# S4_Power_Supply.net
KiCad netlist of a schematic drawn in Altium Designer
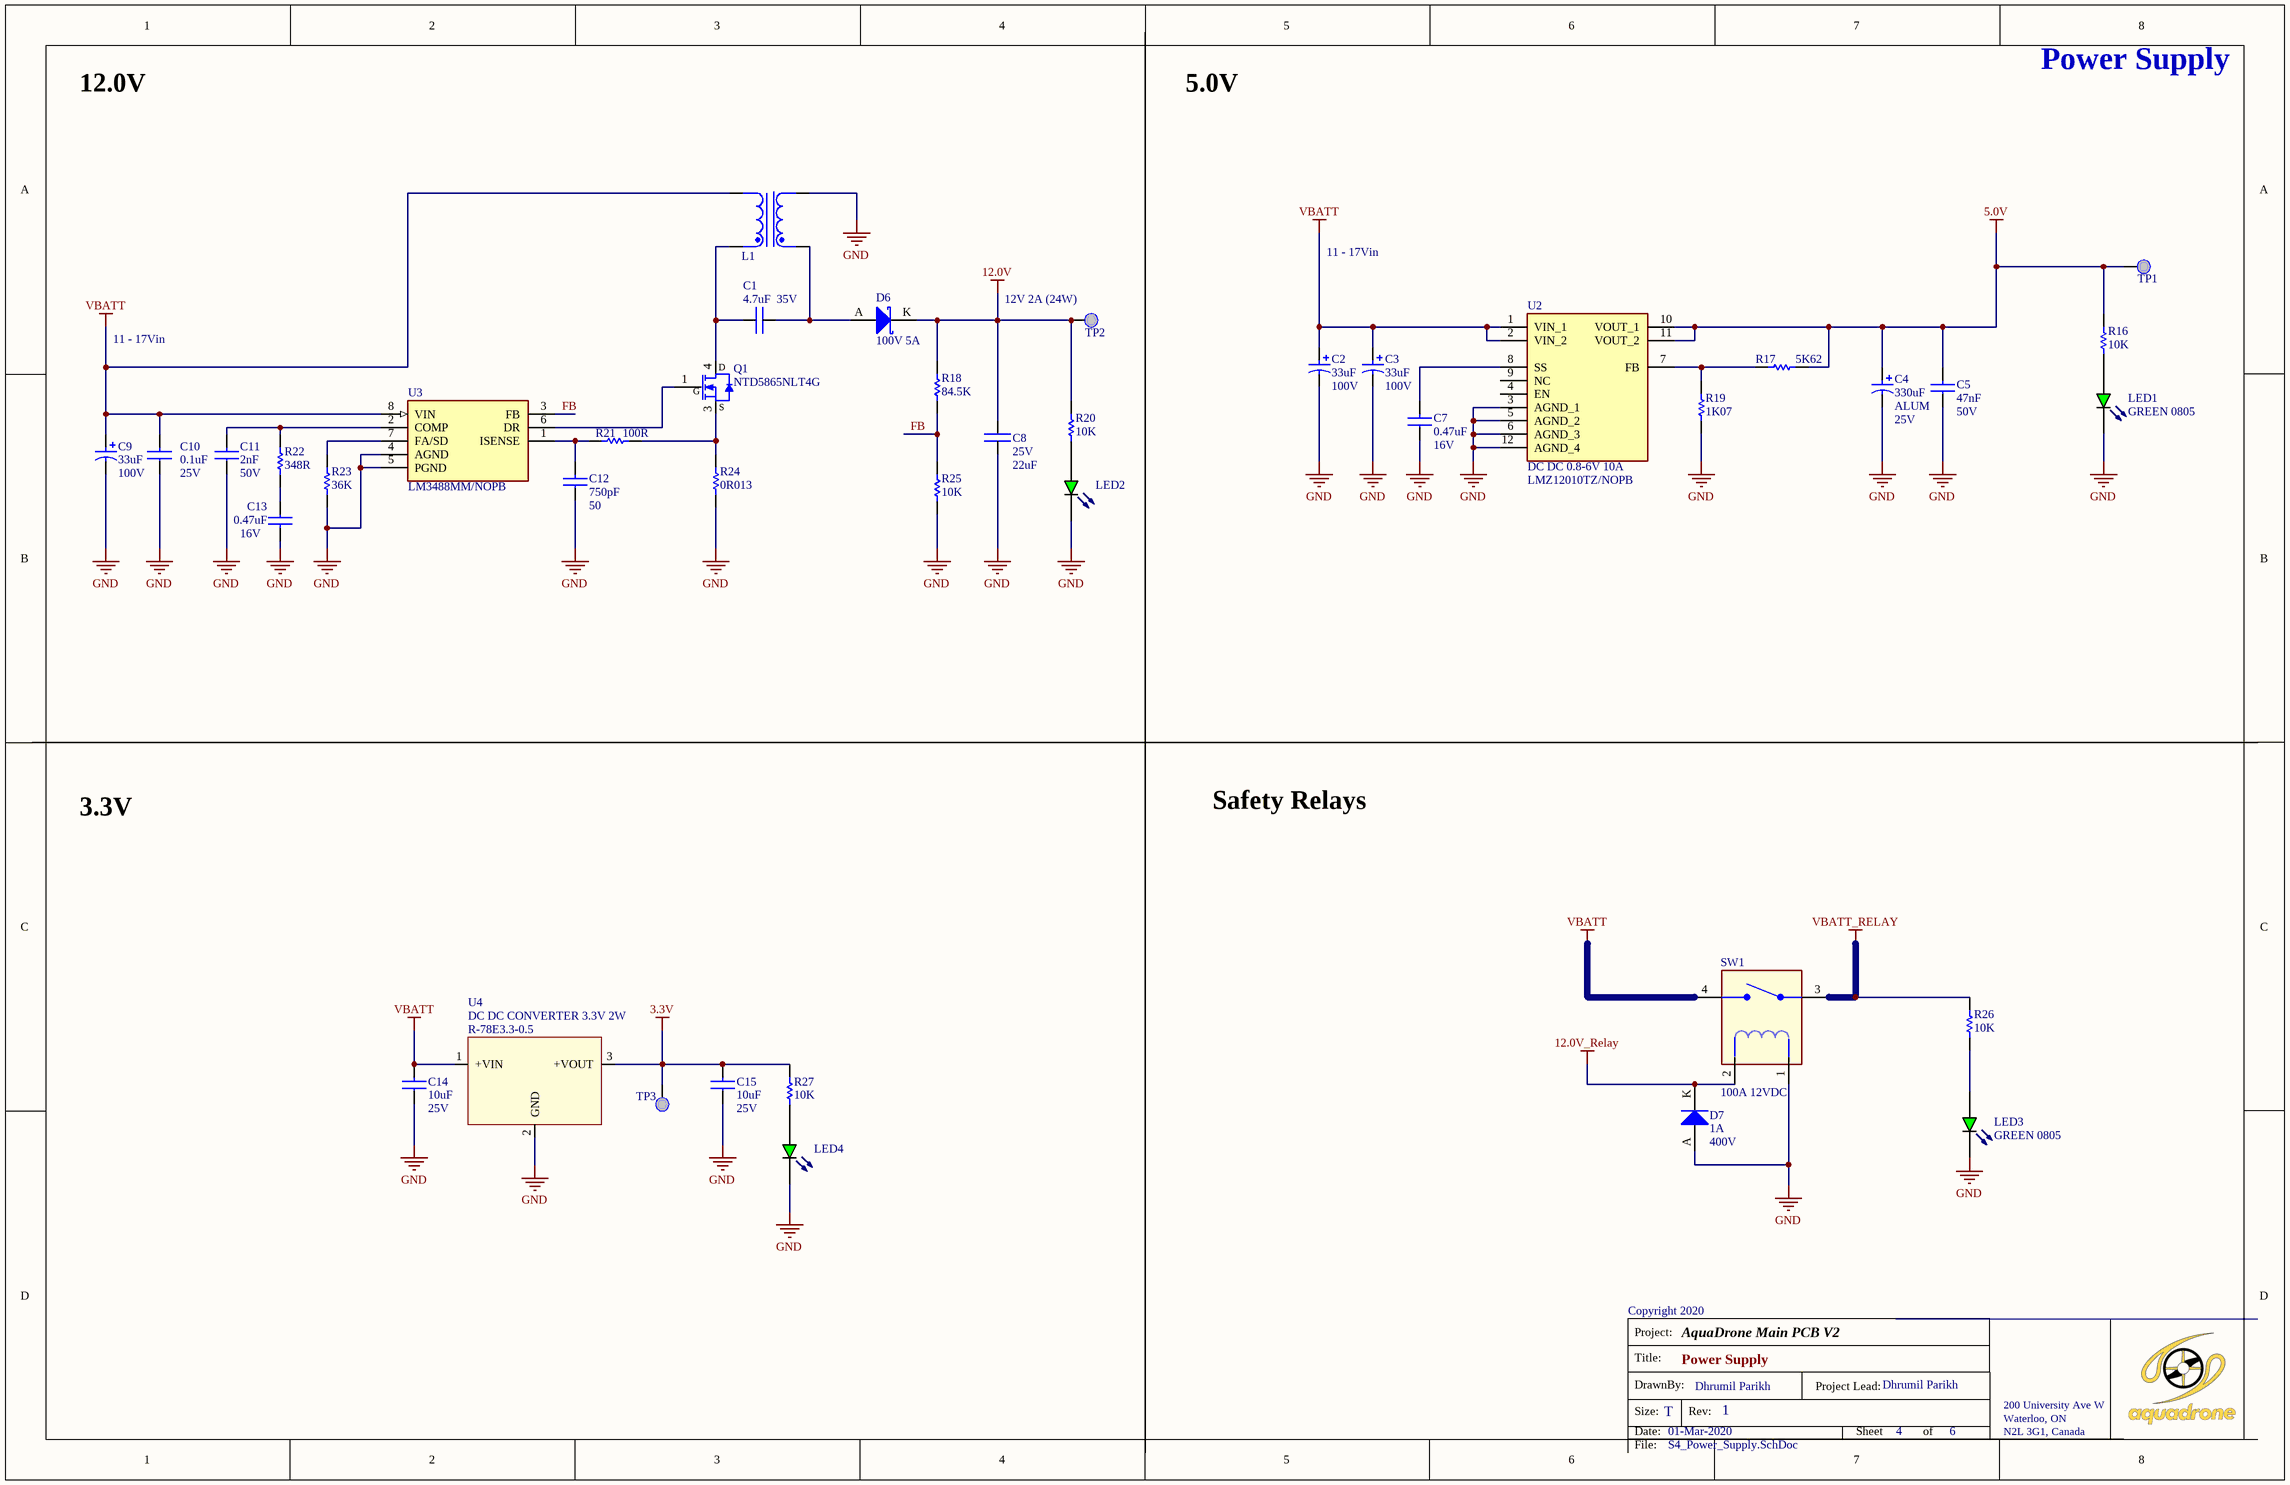
[diagram p0: S4_Power_Supply.SchDoc]

(export (version "E")
  (design (tool "Eeschema 10.0.6"))
  (components
    (comp (ref "C1")
      (value "4.7uF")
      (footprint "RWMN:CAPC2012X14N")
      (description "CAP CER 4.7UF 35V X5R 0805")
      (fields
        (field (name "MFG") "Murata Electronics")
        (field (name "MFG_PART_NO") "GRM219R6YA475KA73D")
        (field (name "VOLTAGE") "35V")
      )
      (libsource (lib "AquaDrone") (part "CAP CER 4.7UF 35V X5R 0805"))
    )
    (comp (ref "C2")
      (value "33uF")
      (footprint "RWMN:CAPPRD350W60D825H1700")
      (description "CAP ALUM 33UF 20% 100V RADIAL")
      (fields
        (field (name "MFG") "Nichicon")
        (field (name "MFG_PART_NO") "UPM2A330MPD1TD")
        (field (name "VOLTAGE") "100V")
      )
      (libsource (lib "AquaDrone") (part "CAP ALUM 33UF 20% 100V RADIAL"))
    )
    (comp (ref "C3")
      (value "33uF")
      (footprint "RWMN:CAPPRD350W60D825H1700")
      (description "CAP ALUM 33UF 20% 100V RADIAL")
      (fields
        (field (name "MFG") "Nichicon")
        (field (name "MFG_PART_NO") "UPM2A330MPD1TD")
        (field (name "VOLTAGE") "100V")
      )
      (libsource (lib "AquaDrone") (part "CAP ALUM 33UF 20% 100V RADIAL"))
    )
    (comp (ref "C4")
      (value "330uF")
      (footprint "RWMN:CAPPRD350W60D850H1300")
      (description "CAP ALUM 330UF 20% 25V TH")
      (fields
        (field (name "MFG") "KEMET")
        (field (name "MFG_PART_NO") "ESL337M025AGMAA")
        (field (name "DIELECTRIC") "ALUM")
        (field (name "VOLTAGE") "25V")
      )
      (libsource (lib "AquaDrone") (part "CAP ALUM 330UF 20% 25V TH"))
    )
    (comp (ref "C5")
      (value "47nF")
      (footprint "RWMN:CAPC1608X09N")
      (description "CAP CER 0.047UF 50V X7R 0603")
      (fields
        (field (name "MFG") "Yageo")
        (field (name "MFG_PART_NO") "CC0603KRX7R9BB473")
        (field (name "VOLTAGE") "50V")
      )
      (libsource (lib "AquaDrone") (part "CAP CER 0.047UF 50V X7R 0603"))
    )
    (comp (ref "C7")
      (value "0.47uF")
      (footprint "RWMN:CAPC1608X09N")
      (description "CAP CER 0.47UF 16V X7R 0603")
      (fields
        (field (name "MFG") "Samsung")
        (field (name "MFG_PART_NO") "CL10B474KO8NNNC")
        (field (name "VOLTAGE") "16V")
      )
      (libsource (lib "AquaDrone") (part "CAP CER 0.47UF 16V X7R 0603"))
    )
    (comp (ref "C8")
      (value "22uF")
      (footprint "RWMN:CAPC3225X28N")
      (description "CAP CER 22UF 25V X7R 1210")
      (fields
        (field (name "MFG") "Taiyo Yuden")
        (field (name "MFG_PART_NO") "TMK325B7226KMHP")
        (field (name "VOLTAGE") "25V")
      )
      (libsource (lib "AquaDrone") (part "CAP CER 22UF 25V X7R 1210"))
    )
    (comp (ref "C9")
      (value "33uF")
      (footprint "RWMN:CAPPRD350W60D825H1700")
      (description "CAP ALUM 33UF 20% 100V RADIAL")
      (fields
        (field (name "MFG") "Nichicon")
        (field (name "MFG_PART_NO") "UPM2A330MPD1TD")
        (field (name "VOLTAGE") "100V")
      )
      (libsource (lib "AquaDrone") (part "CAP ALUM 33UF 20% 100V RADIAL"))
    )
    (comp (ref "C10")
      (value "0.1uF")
      (footprint "RWMN:CAPC1608X09N")
      (description "CAP CER 0.1UF 25V X7R 0603")
      (fields
        (field (name "MFG") "Yageo")
        (field (name "MFG_PART_NO") "CC0603KRX7R8BB104")
        (field (name "VOLTAGE") "25V")
      )
      (libsource (lib "AquaDrone") (part "CAP CER 0.1UF 25V X7R 0603"))
    )
    (comp (ref "C11")
      (value "2nF")
      (footprint "RWMN:CAPC1608X09N")
      (description "CAP CER 2000PF 50V X7R 0603")
      (fields
        (field (name "MFG") "Yageo")
        (field (name "MFG_PART_NO") "CC0603KRX7R9BB202")
        (field (name "VOLTAGE") "50V")
      )
      (libsource (lib "AquaDrone") (part "CAP CER 2000PF 50V X7R 0603"))
    )
    (comp (ref "C12")
      (value "750pF")
      (footprint "RWMN:CAPC1608X09N")
      (description "CAP CER 750PF 50V X7R 0603")
      (fields
        (field (name "MFG") "Yageo")
        (field (name "MFG_PART_NO") "CC0603KRX7R9BB751")
        (field (name "VOLTAGE") "50")
      )
      (libsource (lib "AquaDrone") (part "CAP CER 750PF 50V X7R 0603"))
    )
    (comp (ref "C13")
      (value "0.47uF")
      (footprint "RWMN:CAPC1608X09N")
      (description "CAP CER 0.47UF 16V X7R 0603")
      (fields
        (field (name "MFG") "Samsung")
        (field (name "MFG_PART_NO") "CL10B474KO8NNNC")
        (field (name "VOLTAGE") "16V")
      )
      (libsource (lib "AquaDrone") (part "CAP CER 0.47UF 16V X7R 0603"))
    )
    (comp (ref "C14")
      (value "10uF")
      (footprint "RWMN:CAPC1608X09N")
      (description "CAP CER 10UF 25V X5R 0603")
      (fields
        (field (name "MFG") "KEMET")
        (field (name "MFG_PART_NO") "C1608X5R1E106M080AC")
        (field (name "VOLTAGE") "25V")
      )
      (libsource (lib "AquaDrone") (part "CAP CER 10UF 25V X5R 0603"))
    )
    (comp (ref "C15")
      (value "10uF")
      (footprint "RWMN:CAPC1608X09N")
      (description "CAP CER 10UF 25V X5R 0603")
      (fields
        (field (name "MFG") "KEMET")
        (field (name "MFG_PART_NO") "C1608X5R1E106M080AC")
        (field (name "VOLTAGE") "25V")
      )
      (libsource (lib "AquaDrone") (part "CAP CER 10UF 25V X5R 0603"))
    )
    (comp (ref "D6")
      (value "100V 5A")
      (footprint "SODFL5226X100N")
      (description "DIODE SCHOTTKY 100V 5A DO221AC")
      (fields (field (name "MFG") "Vishay") (field (name "MFG_PART_NO") "VSSAF510-M3/H"))
      (libsource (lib "AquaDrone") (part "DIODE SCHOTTKY 100V 5A DO221AC"))
    )
    (comp (ref "D7")
      (value "DIODE GEN PURP 400V 1A SMA")
      (footprint "DIOM5226X295N")
      (fields
        (field (name "MFG") "SMC Diode Solutions")
        (field (name "MFG_PART_NO") "S1GTR")
        (field (name "CURRENT") "1A")
        (field (name "VR") "400V")
      )
      (libsource (lib "AquaDrone") (part "DIODE GEN PURP 400V 1A SMA"))
    )
    (comp (ref "L1")
      (value "INDUCT ARRAY 2 COIL 9.654UH SMD")
      (footprint "DRQ125100R")
      (fields (field (name "MFG") "Eaton") (field (name "MFG_PART_NO") "DRQ125-100-R"))
      (libsource (lib "AquaDrone") (part "INDUCT ARRAY 2 COIL 9.654UH SMD"))
    )
    (comp (ref "LED1")
      (value "GREEN 0805")
      (footprint "LED0805")
      (description "LED GREEN CLEAR 0805 SMD")
      (fields (field (name "MFG") "Würth Elektronik") (field (name "MFG_PART_NO") "150080VS75000"))
      (libsource (lib "AquaDrone") (part "LED GREEN CLEAR 0805 SMD"))
    )
    (comp (ref "LED2")
      (value "LED GREEN CLEAR 0805 SMD")
      (footprint "LED0805")
      (fields (field (name "MFG") "Würth Elektronik") (field (name "MFG_PART_NO") "150080VS75000"))
      (libsource (lib "AquaDrone") (part "LED GREEN CLEAR 0805 SMD"))
    )
    (comp (ref "LED3")
      (value "GREEN 0805")
      (footprint "LED0805")
      (description "LED GREEN CLEAR 0805 SMD")
      (fields (field (name "MFG") "Würth Elektronik") (field (name "MFG_PART_NO") "150080VS75000"))
      (libsource (lib "AquaDrone") (part "LED GREEN CLEAR 0805 SMD"))
    )
    (comp (ref "LED4")
      (value "LED GREEN CLEAR 0805 SMD")
      (footprint "LED0805")
      (fields (field (name "MFG") "Würth Elektronik") (field (name "MFG_PART_NO") "150080VS75000"))
      (libsource (lib "AquaDrone") (part "LED GREEN CLEAR 0805 SMD"))
    )
    (comp (ref "Q1")
      (value "MOSFET N-CH 60V 46A DPAK")
      (footprint "TO229P990X238-4N")
      (fields (field (name "MFG") "ON Semiconductor") (field (name "MFG_PART_NO") "NTD5865NLT4G"))
      (libsource (lib "AquaDrone") (part "MOSFET N-CH 60V 46A DPAK"))
    )
    (comp (ref "R16")
      (value "10K")
      (footprint "RESC1608X06N")
      (description "RES SMD 10K OHM 1% 1/10W 0603")
      (fields (field (name "MFG") "Vishay Dale") (field (name "MFG_PART_NO") "CRCW060310K0FKEA"))
      (libsource (lib "AquaDrone") (part "RES SMD 10K OHM 1% 1/10W 0603"))
    )
    (comp (ref "R17")
      (value "5K62")
      (footprint "RESC1608X06N")
      (description "RES SMD 5.62K OHM 1% 1/10W 0603")
      (fields (field (name "MFG") "Yageo") (field (name "MFG_PART_NO") "RC0603FR-075K62L"))
      (libsource (lib "AquaDrone") (part "RES SMD 5.62K OHM 1% 1/10W 0603"))
    )
    (comp (ref "R18")
      (value "84.5K")
      (footprint "RESC1608X06N")
      (description "RES SMD 84.5K OHM 1% 1/10W 0603")
      (fields (field (name "MFG") "Yageo") (field (name "MFG_PART_NO") "RC0603FR-0784K5L"))
      (libsource (lib "AquaDrone") (part "RES SMD 84.5K OHM 1% 1/10W 0603"))
    )
    (comp (ref "R19")
      (value "1K07")
      (footprint "RESC1608X06N")
      (description "RES SMD 1.07K OHM 1% 1/10W 0603")
      (fields (field (name "MFG") "Yageo") (field (name "MFG_PART_NO") "RC0603FR-071K07L"))
      (libsource (lib "AquaDrone") (part "RES SMD 1.07K OHM 1% 1/10W 0603"))
    )
    (comp (ref "R20")
      (value "10K")
      (footprint "RESC1608X06N")
      (description "RES SMD 10K OHM 1% 1/10W 0603")
      (fields (field (name "MFG") "Vishay Dale") (field (name "MFG_PART_NO") "CRCW060310K0FKEA"))
      (libsource (lib "AquaDrone") (part "RES SMD 10K OHM 1% 1/10W 0603"))
    )
    (comp (ref "R21")
      (value "100R")
      (footprint "RESC1608X06N")
      (description "RES SMD 100 OHM 1% 1/10W 0603")
      (fields (field (name "MFG") "Yageo") (field (name "MFG_PART_NO") "RC0603FR-07100RL"))
      (libsource (lib "AquaDrone") (part "RES SMD 100 OHM 1% 1/10W 0603"))
    )
    (comp (ref "R22")
      (value "348R")
      (footprint "RESC1608X06N")
      (description "RES SMD 348 OHM 1% 1/10W 0603")
      (fields (field (name "MFG") "Yageo") (field (name "MFG_PART_NO") "RC0603FR-07348RL"))
      (libsource (lib "AquaDrone") (part "RES SMD 348 OHM 1% 1/10W 0603"))
    )
    (comp (ref "R23")
      (value "36K")
      (footprint "RESC1608X06N")
      (description "RES SMD 36K OHM 1% 0.15W 0603")
      (fields (field (name "MFG") "Yageo") (field (name "MFG_PART_NO") "RC0603FR-0736KL"))
      (libsource (lib "AquaDrone") (part "RES SMD 36K OHM 1% 0.15W 0603"))
    )
    (comp (ref "R24")
      (value "0R013")
      (footprint "RESC1632X60N")
      (description "RES 0.013 OHM 1W 1206 WIDE")
      (fields (field (name "MFG") "Susumu") (field (name "MFG_PART_NO") "PRL1632-R013-F-T1"))
      (libsource (lib "AquaDrone") (part "RES 0.013 OHM 1W 1206 WIDE"))
    )
    (comp (ref "R25")
      (value "10K")
      (footprint "RESC1608X06N")
      (description "RES SMD 10K OHM 1% 1/10W 0603")
      (fields (field (name "MFG") "Vishay Dale") (field (name "MFG_PART_NO") "CRCW060310K0FKEA"))
      (libsource (lib "AquaDrone") (part "RES SMD 10K OHM 1% 1/10W 0603"))
    )
    (comp (ref "R26")
      (value "10K")
      (footprint "RESC1608X06N")
      (description "RES SMD 10K OHM 1% 1/10W 0603")
      (fields (field (name "MFG") "Vishay Dale") (field (name "MFG_PART_NO") "CRCW060310K0FKEA"))
      (libsource (lib "AquaDrone") (part "RES SMD 10K OHM 1% 1/10W 0603"))
    )
    (comp (ref "R27")
      (value "10K")
      (footprint "RESC1608X06N")
      (description "RES SMD 10K OHM 1% 1/10W 0603")
      (fields (field (name "MFG") "Vishay Dale") (field (name "MFG_PART_NO") "CRCW060310K0FKEA"))
      (libsource (lib "AquaDrone") (part "RES SMD 10K OHM 1% 1/10W 0603"))
    )
    (comp (ref "SW1")
      (value "100A 12VDC")
      (footprint "G7EB-1A DC12")
      (description "RELAY GEN PURPOSE SPST-NO 100A 12VDC")
      (fields (field (name "MFG") "Omron") (field (name "MFG_PART_NO") "G7EB-1A DC12"))
      (libsource (lib "AquaDrone") (part "RELAY GEN PURPOSE SPST-NO 100A 12VDC"))
    )
    (comp (ref "TP1")
      (value "Testpoint 1mm SMD Pad")
      (footprint "TP_SMD_1.0MM")
      (description "Testpoint 1.0mm SMD Pad")
      (libsource (lib "AquaDrone") (part "Testpoint 1mm SMD Pad"))
    )
    (comp (ref "TP2")
      (value "Testpoint 1mm SMD Pad")
      (footprint "TP_SMD_1.0MM")
      (description "Testpoint 1.0mm SMD Pad")
      (libsource (lib "AquaDrone") (part "Testpoint 1mm SMD Pad"))
    )
    (comp (ref "TP3")
      (value "Testpoint 1mm SMD Pad")
      (footprint "TP_SMD_1.0MM")
      (description "Testpoint 1.0mm SMD Pad")
      (libsource (lib "AquaDrone") (part "Testpoint 1mm SMD Pad"))
    )
    (comp (ref "U2")
      (value "DC DC 0.8-6V 10A")
      (footprint "LMZ12010TZENOPB")
      (description "DC DC CONVERTER 0.8-6V 10A")
      (fields (field (name "MFG") "TI") (field (name "MFG_PART_NO") "LMZ12010TZ/NOPB"))
      (libsource (lib "AquaDrone") (part "DC DC CONVERTER 0.8-6V 10A"))
    )
    (comp (ref "U3")
      (value "IC REG CTRLR MULT TOP 8VSSOP")
      (footprint "SOP65P490X110-8N")
      (fields (field (name "MFG") "TI") (field (name "MFG_PART_NO") "LM3488MM/NOPB"))
      (libsource (lib "AquaDrone") (part "IC REG CTRLR MULT TOP 8VSSOP"))
    )
    (comp (ref "U4")
      (value "DC DC CONVERTER 3.3V 2W")
      (footprint "RWMN:SHDRV3W100P0_254_1X3_1160X850X1040P")
      (fields (field (name "MFG") "Recom Power") (field (name "MFG_PART_NO") "R-78E3.3-0.5"))
      (libsource (lib "AquaDrone") (part "DC DC CONVERTER 3.3V 2W"))
    )
  )
  (nets
    (net (code "1") (name "/FB") (class "Default")
      (node (ref "R18") (pin "1") (pinfunction "1_1") (pintype "passive"))
      (node (ref "R25") (pin "2") (pinfunction "2_2") (pintype "passive"))
      (node (ref "U3") (pin "3") (pinfunction "FB_3") (pintype "passive"))
    )
    (net (code "2") (name "3.3V") (class "Default")
      (node (ref "C15") (pin "2") (pinfunction "2_2") (pintype "passive"))
      (node (ref "R27") (pin "2") (pinfunction "2_2") (pintype "passive"))
      (node (ref "TP3") (pin "1") (pinfunction "1_1") (pintype "passive"))
      (node (ref "U4") (pin "3") (pinfunction "+VOUT_3") (pintype "power_in"))
    )
    (net (code "3") (name "5.0V") (class "Default")
      (node (ref "C4") (pin "1") (pinfunction "1_1") (pintype "passive"))
      (node (ref "C5") (pin "2") (pinfunction "2_2") (pintype "passive"))
      (node (ref "R16") (pin "2") (pinfunction "2_2") (pintype "passive"))
      (node (ref "R17") (pin "2") (pinfunction "2_2") (pintype "passive"))
      (node (ref "TP1") (pin "1") (pinfunction "1_1") (pintype "passive"))
      (node (ref "U2") (pin "10") (pinfunction "VOUT_1_10") (pintype "passive"))
      (node (ref "U2") (pin "11") (pinfunction "VOUT_2_11") (pintype "passive"))
    )
    (net (code "4") (name "12.0V") (class "Default")
      (node (ref "C8") (pin "1") (pinfunction "1_1") (pintype "passive"))
      (node (ref "D6") (pin "K") (pinfunction "K_K") (pintype "passive"))
      (node (ref "R18") (pin "2") (pinfunction "2_2") (pintype "passive"))
      (node (ref "R20") (pin "2") (pinfunction "2_2") (pintype "passive"))
      (node (ref "TP2") (pin "1") (pinfunction "1_1") (pintype "passive"))
    )
    (net (code "5") (name "12.0V_Relay") (class "Default")
      (node (ref "D7") (pin "K") (pinfunction "K_K") (pintype "passive"))
      (node (ref "SW1") (pin "2") (pinfunction "2_2") (pintype "power_in"))
    )
    (net (code "6") (name "GND") (class "Default")
      (node (ref "C10") (pin "1") (pinfunction "1_1") (pintype "passive"))
      (node (ref "C11") (pin "1") (pinfunction "1_1") (pintype "passive"))
      (node (ref "C12") (pin "1") (pinfunction "1_1") (pintype "passive"))
      (node (ref "C13") (pin "2") (pinfunction "2_2") (pintype "passive"))
      (node (ref "C14") (pin "1") (pinfunction "1_1") (pintype "passive"))
      (node (ref "C15") (pin "1") (pinfunction "1_1") (pintype "passive"))
      (node (ref "C2") (pin "2") (pinfunction "2_2") (pintype "passive"))
      (node (ref "C3") (pin "2") (pinfunction "2_2") (pintype "passive"))
      (node (ref "C4") (pin "2") (pinfunction "2_2") (pintype "passive"))
      (node (ref "C5") (pin "1") (pinfunction "1_1") (pintype "passive"))
      (node (ref "C7") (pin "1") (pinfunction "1_1") (pintype "passive"))
      (node (ref "C8") (pin "2") (pinfunction "2_2") (pintype "passive"))
      (node (ref "C9") (pin "2") (pinfunction "2_2") (pintype "passive"))
      (node (ref "D7") (pin "A") (pinfunction "A_A") (pintype "passive"))
      (node (ref "L1") (pin "3") (pinfunction "3_3") (pintype "passive"))
      (node (ref "LED1") (pin "K") (pinfunction "K_K") (pintype "passive"))
      (node (ref "LED2") (pin "K") (pinfunction "K_K") (pintype "passive"))
      (node (ref "LED3") (pin "K") (pinfunction "K_K") (pintype "passive"))
      (node (ref "LED4") (pin "K") (pinfunction "K_K") (pintype "passive"))
      (node (ref "R19") (pin "1") (pinfunction "1_1") (pintype "passive"))
      (node (ref "R23") (pin "1") (pinfunction "1_1") (pintype "passive"))
      (node (ref "R24") (pin "1") (pinfunction "1_1") (pintype "passive"))
      (node (ref "R25") (pin "1") (pinfunction "1_1") (pintype "passive"))
      (node (ref "SW1") (pin "1") (pinfunction "1_1") (pintype "power_in"))
      (node (ref "U2") (pin "12") (pinfunction "AGND_4_12") (pintype "passive"))
      (node (ref "U2") (pin "3") (pinfunction "AGND_1_3") (pintype "passive"))
      (node (ref "U2") (pin "5") (pinfunction "AGND_2_5") (pintype "passive"))
      (node (ref "U2") (pin "6") (pinfunction "AGND_3_6") (pintype "passive"))
      (node (ref "U3") (pin "4") (pinfunction "AGND_4") (pintype "power_in"))
      (node (ref "U3") (pin "5") (pinfunction "PGND_5") (pintype "power_in"))
      (node (ref "U4") (pin "2") (pinfunction "GND_2") (pintype "power_in"))
    )
    (net (code "7") (name "Net-(C1-Pad2)") (class "Default")
      (node (ref "C1") (pin "2") (pinfunction "2_2") (pintype "passive"))
      (node (ref "D6") (pin "A") (pinfunction "A_A") (pintype "passive"))
      (node (ref "L1") (pin "1") (pinfunction "1_1") (pintype "passive"))
    )
    (net (code "8") (name "Net-(C13-Pad1)") (class "Default")
      (node (ref "C13") (pin "1") (pinfunction "1_1") (pintype "passive"))
      (node (ref "R22") (pin "1") (pinfunction "1_1") (pintype "passive"))
    )
    (net (code "9") (name "Net-(LED1-PadA)") (class "Default")
      (node (ref "LED1") (pin "A") (pinfunction "A_A") (pintype "passive"))
      (node (ref "R16") (pin "1") (pinfunction "1_1") (pintype "passive"))
    )
    (net (code "10") (name "Net-(LED2-PadA)") (class "Default")
      (node (ref "LED2") (pin "A") (pinfunction "A_A") (pintype "passive"))
      (node (ref "R20") (pin "1") (pinfunction "1_1") (pintype "passive"))
    )
    (net (code "11") (name "Net-(LED3-PadA)") (class "Default")
      (node (ref "LED3") (pin "A") (pinfunction "A_A") (pintype "passive"))
      (node (ref "R26") (pin "1") (pinfunction "1_1") (pintype "passive"))
    )
    (net (code "12") (name "Net-(LED4-PadA)") (class "Default")
      (node (ref "LED4") (pin "A") (pinfunction "A_A") (pintype "passive"))
      (node (ref "R27") (pin "1") (pinfunction "1_1") (pintype "passive"))
    )
    (net (code "13") (name "Net-(Q1-D)") (class "Default")
      (node (ref "C1") (pin "1") (pinfunction "1_1") (pintype "passive"))
      (node (ref "L1") (pin "2") (pinfunction "2_2") (pintype "passive"))
      (node (ref "Q1") (pin "4") (pinfunction "D_4") (pintype "power_in"))
    )
    (net (code "14") (name "Net-(Q1-G)") (class "Default")
      (node (ref "Q1") (pin "1") (pinfunction "G_1") (pintype "tri_state"))
      (node (ref "U3") (pin "6") (pinfunction "DR_6") (pintype "passive"))
    )
    (net (code "15") (name "Net-(Q1-S)") (class "Default")
      (node (ref "Q1") (pin "3") (pinfunction "S_3") (pintype "power_in"))
      (node (ref "R21") (pin "2") (pinfunction "2_2") (pintype "passive"))
      (node (ref "R24") (pin "2") (pinfunction "2_2") (pintype "passive"))
    )
    (net (code "16") (name "Net-(U2-FB)") (class "Default")
      (node (ref "R17") (pin "1") (pinfunction "1_1") (pintype "passive"))
      (node (ref "R19") (pin "2") (pinfunction "2_2") (pintype "passive"))
      (node (ref "U2") (pin "7") (pinfunction "FB_7") (pintype "passive"))
    )
    (net (code "17") (name "Net-(U2-SS)") (class "Default")
      (node (ref "C7") (pin "2") (pinfunction "2_2") (pintype "passive"))
      (node (ref "U2") (pin "8") (pinfunction "SS_8") (pintype "passive"))
    )
    (net (code "18") (name "Net-(U3-COMP)") (class "Default")
      (node (ref "C11") (pin "2") (pinfunction "2_2") (pintype "passive"))
      (node (ref "R22") (pin "2") (pinfunction "2_2") (pintype "passive"))
      (node (ref "U3") (pin "2") (pinfunction "COMP_2") (pintype "passive"))
    )
    (net (code "19") (name "Net-(U3-FA{slash}SD)") (class "Default")
      (node (ref "R23") (pin "2") (pinfunction "2_2") (pintype "passive"))
      (node (ref "U3") (pin "7") (pinfunction "FA/SD_7") (pintype "passive"))
    )
    (net (code "20") (name "Net-(U3-ISENSE)") (class "Default")
      (node (ref "C12") (pin "2") (pinfunction "2_2") (pintype "passive"))
      (node (ref "R21") (pin "1") (pinfunction "1_1") (pintype "passive"))
      (node (ref "U3") (pin "1") (pinfunction "ISENSE_1") (pintype "passive"))
    )
    (net (code "21") (name "VBATT") (class "Default")
      (node (ref "C10") (pin "2") (pinfunction "2_2") (pintype "passive"))
      (node (ref "C14") (pin "2") (pinfunction "2_2") (pintype "passive"))
      (node (ref "C2") (pin "1") (pinfunction "1_1") (pintype "passive"))
      (node (ref "C3") (pin "1") (pinfunction "1_1") (pintype "passive"))
      (node (ref "C9") (pin "1") (pinfunction "1_1") (pintype "passive"))
      (node (ref "L1") (pin "4") (pinfunction "4_4") (pintype "passive"))
      (node (ref "SW1") (pin "4") (pinfunction "4_4") (pintype "power_in"))
      (node (ref "U2") (pin "1") (pinfunction "VIN_1_1") (pintype "passive"))
      (node (ref "U2") (pin "2") (pinfunction "VIN_2_2") (pintype "passive"))
      (node (ref "U3") (pin "8") (pinfunction "VIN_8") (pintype "input"))
      (node (ref "U4") (pin "1") (pinfunction "+VIN_1") (pintype "power_in"))
    )
    (net (code "22") (name "VBATT_RELAY") (class "Default")
      (node (ref "R26") (pin "2") (pinfunction "2_2") (pintype "passive"))
      (node (ref "SW1") (pin "3") (pinfunction "3_3") (pintype "power_in"))
    )
    (net (code "23") (name "unconnected-(U2-EN-Pad4)") (class "Default")
      (node (ref "U2") (pin "4") (pinfunction "EN_4") (pintype "passive"))
    )
    (net (code "24") (name "unconnected-(U2-NC-Pad9)") (class "Default")
      (node (ref "U2") (pin "9") (pinfunction "NC_9") (pintype "passive"))
    )
  )
)
